# Cthulhu_Shield_Rev2f.net
KiCad netlist of a schematic drawn in EAGLE
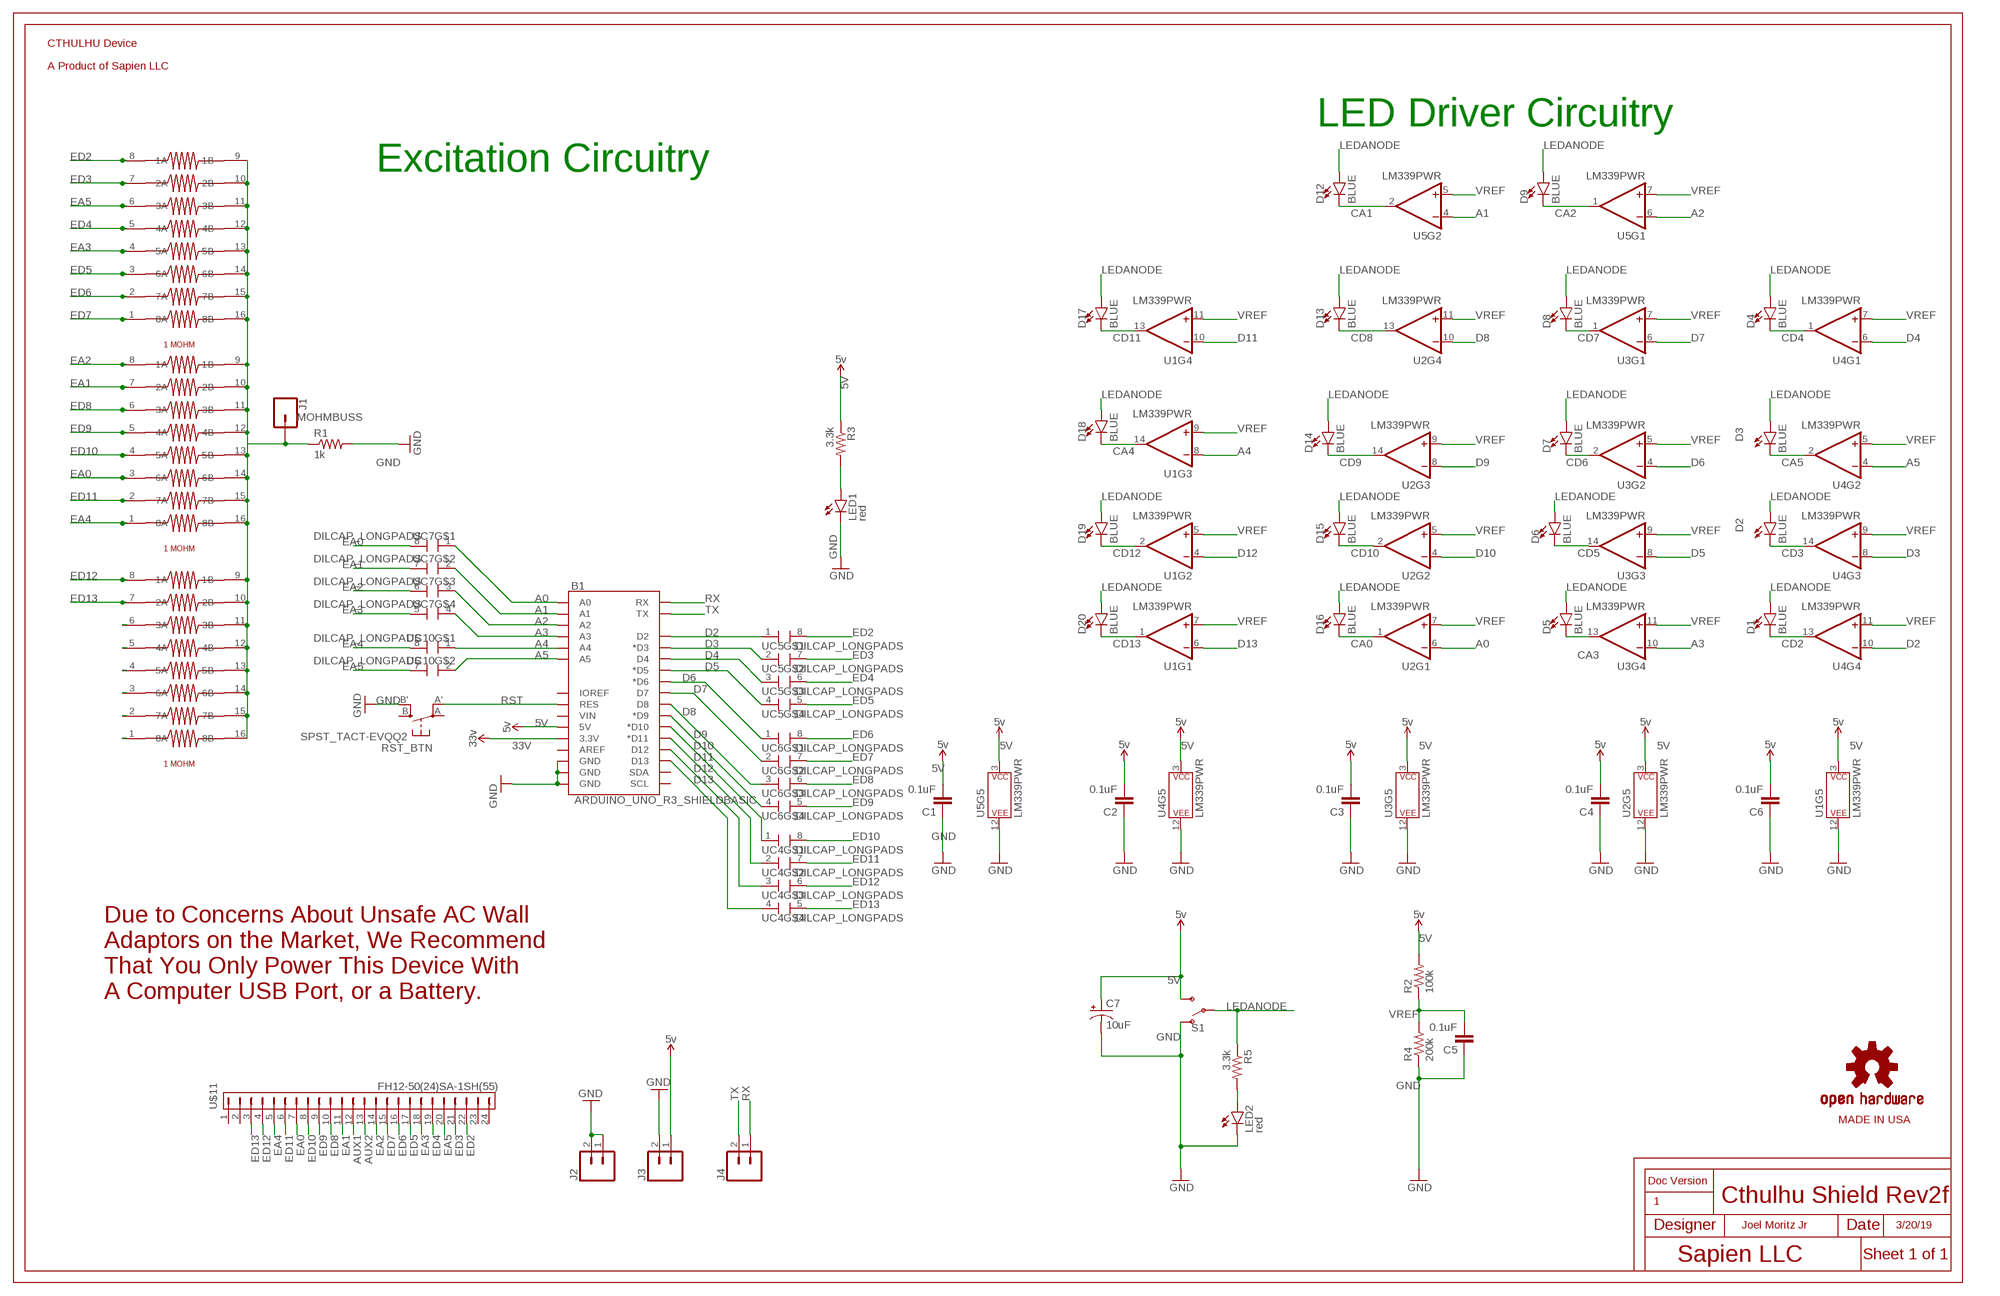
[diagram p0: schematic, sheet 1]

(export (version "E")
  (design (tool "Eeschema 10.0.6"))
  (components
    (comp (ref "B1")
      (value "ARDUINO_UNO_R3_SHIELDBASIC")
      (footprint "eagle-import:UNO_R3_SHIELD")
      (libsource (lib "eagle-import") (part "ARDUINO_UNO_R3_SHIELDBASIC"))
    )
    (comp (ref "C1")
      (value "0.1uF")
      (footprint "eagle-import:0603")
      (libsource (lib "eagle-import") (part "0.1UF-0603-25V-(+80/-20%)"))
    )
    (comp (ref "C2")
      (value "0.1uF")
      (footprint "eagle-import:0603")
      (libsource (lib "eagle-import") (part "0.1UF-0603-25V-(+80/-20%)"))
    )
    (comp (ref "C3")
      (value "0.1uF")
      (footprint "eagle-import:0603")
      (libsource (lib "eagle-import") (part "0.1UF-0603-25V-(+80/-20%)"))
    )
    (comp (ref "C4")
      (value "0.1uF")
      (footprint "eagle-import:0603")
      (libsource (lib "eagle-import") (part "0.1UF-0603-25V-(+80/-20%)"))
    )
    (comp (ref "C5")
      (value "0.1uF")
      (footprint "eagle-import:0603")
      (libsource (lib "eagle-import") (part "0.1UF-0603-25V-(+80/-20%)"))
    )
    (comp (ref "C6")
      (value "0.1uF")
      (footprint "eagle-import:0603")
      (libsource (lib "eagle-import") (part "0.1UF-0603-25V-(+80/-20%)"))
    )
    (comp (ref "C7")
      (value "10uF")
      (footprint "eagle-import:EIA3528")
      (libsource (lib "eagle-import") (part "10UF-POLAR-EIA3528-20V-10%(TANT)"))
    )
    (comp (ref "D1")
      (value "BLUE")
      (footprint "eagle-import:LED-0603")
      (libsource (lib "eagle-import") (part "LED-BLUE0603"))
    )
    (comp (ref "D2")
      (value "BLUE")
      (footprint "eagle-import:LED-0603")
      (libsource (lib "eagle-import") (part "LED-BLUE0603"))
    )
    (comp (ref "D3")
      (value "BLUE")
      (footprint "eagle-import:LED-0603")
      (libsource (lib "eagle-import") (part "LED-BLUE0603"))
    )
    (comp (ref "D4")
      (value "BLUE")
      (footprint "eagle-import:LED-0603")
      (libsource (lib "eagle-import") (part "LED-BLUE0603"))
    )
    (comp (ref "D5")
      (value "BLUE")
      (footprint "eagle-import:LED-0603")
      (libsource (lib "eagle-import") (part "LED-BLUE0603"))
    )
    (comp (ref "D6")
      (value "BLUE")
      (footprint "eagle-import:LED-0603")
      (libsource (lib "eagle-import") (part "LED-BLUE0603"))
    )
    (comp (ref "D7")
      (value "BLUE")
      (footprint "eagle-import:LED-0603")
      (libsource (lib "eagle-import") (part "LED-BLUE0603"))
    )
    (comp (ref "D8")
      (value "BLUE")
      (footprint "eagle-import:LED-0603")
      (libsource (lib "eagle-import") (part "LED-BLUE0603"))
    )
    (comp (ref "D9")
      (value "BLUE")
      (footprint "eagle-import:LED-0603")
      (libsource (lib "eagle-import") (part "LED-BLUE0603"))
    )
    (comp (ref "D12")
      (value "BLUE")
      (footprint "eagle-import:LED-0603")
      (libsource (lib "eagle-import") (part "LED-BLUE0603"))
    )
    (comp (ref "D13")
      (value "BLUE")
      (footprint "eagle-import:LED-0603")
      (libsource (lib "eagle-import") (part "LED-BLUE0603"))
    )
    (comp (ref "D14")
      (value "BLUE")
      (footprint "eagle-import:LED-0603")
      (libsource (lib "eagle-import") (part "LED-BLUE0603"))
    )
    (comp (ref "D15")
      (value "BLUE")
      (footprint "eagle-import:LED-0603")
      (libsource (lib "eagle-import") (part "LED-BLUE0603"))
    )
    (comp (ref "D16")
      (value "BLUE")
      (footprint "eagle-import:LED-0603")
      (libsource (lib "eagle-import") (part "LED-BLUE0603"))
    )
    (comp (ref "D17")
      (value "BLUE")
      (footprint "eagle-import:LED-0603")
      (libsource (lib "eagle-import") (part "LED-BLUE0603"))
    )
    (comp (ref "D18")
      (value "BLUE")
      (footprint "eagle-import:LED-0603")
      (libsource (lib "eagle-import") (part "LED-BLUE0603"))
    )
    (comp (ref "D19")
      (value "BLUE")
      (footprint "eagle-import:LED-0603")
      (libsource (lib "eagle-import") (part "LED-BLUE0603"))
    )
    (comp (ref "D20")
      (value "BLUE")
      (footprint "eagle-import:LED-0603")
      (libsource (lib "eagle-import") (part "LED-BLUE0603"))
    )
    (comp (ref "J1")
      (value "CONN_01")
      (footprint "eagle-import:1X01")
      (libsource (lib "eagle-import") (part "CONN_01"))
    )
    (comp (ref "J2")
      (value "CONN_02")
      (footprint "eagle-import:1X02")
      (libsource (lib "eagle-import") (part "CONN_02"))
    )
    (comp (ref "J3")
      (value "CONN_02")
      (footprint "eagle-import:1X02")
      (libsource (lib "eagle-import") (part "CONN_02"))
    )
    (comp (ref "J4")
      (value "CONN_02")
      (footprint "eagle-import:1X02")
      (libsource (lib "eagle-import") (part "CONN_02"))
    )
    (comp (ref "LED1")
      (value "red")
      (footprint "eagle-import:LED-1206")
      (libsource (lib "eagle-import") (part "LED1206"))
    )
    (comp (ref "LED2")
      (value "red")
      (footprint "eagle-import:LED-1206")
      (libsource (lib "eagle-import") (part "LED1206"))
    )
    (comp (ref "LOGO1")
      (value "OSHW-LOGOL")
      (footprint "eagle-import:OSHW-LOGO-L")
      (libsource (lib "eagle-import") (part "OSHW-LOGOL"))
    )
    (comp (ref "R1")
      (value "1k")
      (footprint "eagle-import:0402")
      (libsource (lib "eagle-import") (part "RESISTOR0402"))
    )
    (comp (ref "R2")
      (value "100k")
      (footprint "eagle-import:0402")
      (libsource (lib "eagle-import") (part "RESISTOR0402"))
    )
    (comp (ref "R3")
      (value "3.3k")
      (footprint "eagle-import:0402")
      (libsource (lib "eagle-import") (part "RESISTOR0402"))
    )
    (comp (ref "R4")
      (value "200k")
      (footprint "eagle-import:0402")
      (libsource (lib "eagle-import") (part "RESISTOR0402"))
    )
    (comp (ref "R5")
      (value "3.3k")
      (footprint "eagle-import:0402")
      (libsource (lib "eagle-import") (part "RESISTOR0402"))
    )
    (comp (ref "RST_BTN")
      (value "SPST_TACT-EVQQ2")
      (footprint "eagle-import:EVQ-Q2")
      (libsource (lib "eagle-import") (part "SPST_TACT-EVQQ2"))
    )
    (comp (ref "S1")
      (value "SWITCH-SPDT-SMD-AYZ0202")
      (footprint "eagle-import:SWITCH_DPDT_SMD_AYZ0202")
      (libsource (lib "eagle-import") (part "SWITCH-SPDT-SMD-AYZ0202"))
    )
    (comp (ref "U$1")
      (value "1MOHM8")
      (footprint "eagle-import:JJ_CUSTOM_PARTS_1MOHMARRAY")
      (libsource (lib "eagle-import") (part "1MOHM8"))
    )
    (comp (ref "U$2")
      (value "1MOHM8")
      (footprint "eagle-import:JJ_CUSTOM_PARTS_1MOHMARRAY")
      (libsource (lib "eagle-import") (part "1MOHM8"))
    )
    (comp (ref "U$3")
      (value "1MOHM8")
      (footprint "eagle-import:JJ_CUSTOM_PARTS_1MOHMARRAY")
      (libsource (lib "eagle-import") (part "1MOHM8"))
    )
    (comp (ref "U$4")
      (value "NO_WALL_ADAPTOR")
      (footprint "eagle-import:NO_WALL_ADAPTOR")
      (libsource (lib "eagle-import") (part "NO_WALL_ADAPTOR"))
    )
    (comp (ref "U$5")
      (value "MADEINUSA")
      (footprint "eagle-import:MADEINUSA")
      (libsource (lib "eagle-import") (part "MADEINUSA"))
    )
    (comp (ref "U$8")
      (value "SAPEIN_LOGO_BOTTOM")
      (footprint "eagle-import:SAPIEN_LOGO_BOTTOM")
      (libsource (lib "eagle-import") (part "SAPEIN_LOGO_BOTTOM"))
    )
    (comp (ref "U$9")
      (value "CTHULHU_LOGO")
      (footprint "eagle-import:CTHULHU")
      (libsource (lib "eagle-import") (part "CTHULHU_LOGO"))
    )
    (comp (ref "U$11")
      (value "FH12-50(24)SA-1SH(55)")
      (footprint "eagle-import:FH12-16S-1SH")
      (libsource (lib "eagle-import") (part "FH12-50(24)SA-1SH(55)"))
    )
    (comp (ref "U1")
      (value "LM339PWR")
      (footprint "eagle-import:TSSOP-14")
      (libsource (lib "eagle-import") (part "LM339"))
    )
    (comp (ref "U2")
      (value "LM339PWR")
      (footprint "eagle-import:TSSOP-14")
      (libsource (lib "eagle-import") (part "LM339"))
    )
    (comp (ref "U3")
      (value "LM339PWR")
      (footprint "eagle-import:TSSOP-14")
      (libsource (lib "eagle-import") (part "LM339"))
    )
    (comp (ref "U4")
      (value "LM339PWR")
      (footprint "eagle-import:TSSOP-14")
      (libsource (lib "eagle-import") (part "LM339"))
    )
    (comp (ref "U5")
      (value "LM339PWR")
      (footprint "eagle-import:TSSOP-14")
      (libsource (lib "eagle-import") (part "LM339"))
    )
    (comp (ref "UC4")
      (value "DILCAP_LONGPADS")
      (footprint "eagle-import:RESISTOR-DIL_4X0402ARV341_LONGPADS")
      (libsource (lib "eagle-import") (part "DILCAP_LONGPADS"))
    )
    (comp (ref "UC5")
      (value "DILCAP_LONGPADS")
      (footprint "eagle-import:RESISTOR-DIL_4X0402ARV341_LONGPADS")
      (libsource (lib "eagle-import") (part "DILCAP_LONGPADS"))
    )
    (comp (ref "UC6")
      (value "DILCAP_LONGPADS")
      (footprint "eagle-import:RESISTOR-DIL_4X0402ARV341_LONGPADS")
      (libsource (lib "eagle-import") (part "DILCAP_LONGPADS"))
    )
    (comp (ref "UC7")
      (value "DILCAP_LONGPADS")
      (footprint "eagle-import:RESISTOR-DIL_4X0402ARV341_LONGPADS")
      (libsource (lib "eagle-import") (part "DILCAP_LONGPADS"))
    )
    (comp (ref "UC10")
      (value "DILCAP_LONGPADS")
      (footprint "eagle-import:RESISTOR-DIL_4X0402ARV341_LONGPADS")
      (libsource (lib "eagle-import") (part "DILCAP_LONGPADS"))
    )
  )
  (nets
    (net (code "1") (name "/A0") (class "Default")
      (node (ref "B1") (pin "A0") (pinfunction "A0_A0") (pintype "bidirectional"))
      (node (ref "U2") (pin "6") (pinfunction "-IN_6") (pintype "input"))
      (node (ref "UC7") (pin "1") (pinfunction "1_1") (pintype "passive"))
    )
    (net (code "2") (name "/A1") (class "Default")
      (node (ref "B1") (pin "A1") (pinfunction "A1_A1") (pintype "bidirectional"))
      (node (ref "U5") (pin "4") (pinfunction "-IN_4") (pintype "input"))
      (node (ref "UC7") (pin "2") (pinfunction "1_2") (pintype "passive"))
    )
    (net (code "3") (name "/A2") (class "Default")
      (node (ref "B1") (pin "A2") (pinfunction "A2_A2") (pintype "bidirectional"))
      (node (ref "U5") (pin "6") (pinfunction "-IN_6") (pintype "input"))
      (node (ref "UC7") (pin "3") (pinfunction "1_3") (pintype "passive"))
    )
    (net (code "4") (name "/A3") (class "Default")
      (node (ref "B1") (pin "A3") (pinfunction "A3_A3") (pintype "bidirectional"))
      (node (ref "U3") (pin "10") (pinfunction "-IN_10") (pintype "input"))
      (node (ref "UC7") (pin "4") (pinfunction "1_4") (pintype "passive"))
    )
    (net (code "5") (name "/A4") (class "Default")
      (node (ref "B1") (pin "A4") (pinfunction "A4_A4") (pintype "bidirectional"))
      (node (ref "U1") (pin "8") (pinfunction "-IN_8") (pintype "input"))
      (node (ref "UC10") (pin "1") (pinfunction "1_1") (pintype "passive"))
    )
    (net (code "6") (name "/A5") (class "Default")
      (node (ref "B1") (pin "A5") (pinfunction "A5_A5") (pintype "bidirectional"))
      (node (ref "U4") (pin "4") (pinfunction "-IN_4") (pintype "input"))
      (node (ref "UC10") (pin "2") (pinfunction "1_2") (pintype "passive"))
    )
    (net (code "7") (name "/AUX1") (class "Default")
      (node (ref "U$11") (pin "12") (pinfunction "12_12") (pintype "passive"))
    )
    (net (code "8") (name "/AUX2") (class "Default")
      (node (ref "U$11") (pin "13") (pinfunction "13_13") (pintype "passive"))
    )
    (net (code "9") (name "/CA0") (class "Default")
      (node (ref "D16") (pin "C") (pinfunction "C_C") (pintype "passive"))
      (node (ref "U2") (pin "1") (pinfunction "OUT_1") (pintype "output"))
    )
    (net (code "10") (name "/CA1") (class "Default")
      (node (ref "D12") (pin "C") (pinfunction "C_C") (pintype "passive"))
      (node (ref "U5") (pin "2") (pinfunction "OUT_2") (pintype "output"))
    )
    (net (code "11") (name "/CA2") (class "Default")
      (node (ref "D9") (pin "C") (pinfunction "C_C") (pintype "passive"))
      (node (ref "U5") (pin "1") (pinfunction "OUT_1") (pintype "output"))
    )
    (net (code "12") (name "/CA3") (class "Default")
      (node (ref "D5") (pin "C") (pinfunction "C_C") (pintype "passive"))
      (node (ref "U3") (pin "13") (pinfunction "OUT_13") (pintype "output"))
    )
    (net (code "13") (name "/CA4") (class "Default")
      (node (ref "D18") (pin "C") (pinfunction "C_C") (pintype "passive"))
      (node (ref "U1") (pin "14") (pinfunction "OUT_14") (pintype "output"))
    )
    (net (code "14") (name "/CA5") (class "Default")
      (node (ref "D3") (pin "C") (pinfunction "C_C") (pintype "passive"))
      (node (ref "U4") (pin "2") (pinfunction "OUT_2") (pintype "output"))
    )
    (net (code "15") (name "/CD2") (class "Default")
      (node (ref "D1") (pin "C") (pinfunction "C_C") (pintype "passive"))
      (node (ref "U4") (pin "13") (pinfunction "OUT_13") (pintype "output"))
    )
    (net (code "16") (name "/CD3") (class "Default")
      (node (ref "D2") (pin "C") (pinfunction "C_C") (pintype "passive"))
      (node (ref "U4") (pin "14") (pinfunction "OUT_14") (pintype "output"))
    )
    (net (code "17") (name "/CD4") (class "Default")
      (node (ref "D4") (pin "C") (pinfunction "C_C") (pintype "passive"))
      (node (ref "U4") (pin "1") (pinfunction "OUT_1") (pintype "output"))
    )
    (net (code "18") (name "/CD5") (class "Default")
      (node (ref "D6") (pin "C") (pinfunction "C_C") (pintype "passive"))
      (node (ref "U3") (pin "14") (pinfunction "OUT_14") (pintype "output"))
    )
    (net (code "19") (name "/CD6") (class "Default")
      (node (ref "D7") (pin "C") (pinfunction "C_C") (pintype "passive"))
      (node (ref "U3") (pin "2") (pinfunction "OUT_2") (pintype "output"))
    )
    (net (code "20") (name "/CD7") (class "Default")
      (node (ref "D8") (pin "C") (pinfunction "C_C") (pintype "passive"))
      (node (ref "U3") (pin "1") (pinfunction "OUT_1") (pintype "output"))
    )
    (net (code "21") (name "/CD8") (class "Default")
      (node (ref "D13") (pin "C") (pinfunction "C_C") (pintype "passive"))
      (node (ref "U2") (pin "13") (pinfunction "OUT_13") (pintype "output"))
    )
    (net (code "22") (name "/CD9") (class "Default")
      (node (ref "D14") (pin "C") (pinfunction "C_C") (pintype "passive"))
      (node (ref "U2") (pin "14") (pinfunction "OUT_14") (pintype "output"))
    )
    (net (code "23") (name "/CD10") (class "Default")
      (node (ref "D15") (pin "C") (pinfunction "C_C") (pintype "passive"))
      (node (ref "U2") (pin "2") (pinfunction "OUT_2") (pintype "output"))
    )
    (net (code "24") (name "/CD11") (class "Default")
      (node (ref "D17") (pin "C") (pinfunction "C_C") (pintype "passive"))
      (node (ref "U1") (pin "13") (pinfunction "OUT_13") (pintype "output"))
    )
    (net (code "25") (name "/CD12") (class "Default")
      (node (ref "D19") (pin "C") (pinfunction "C_C") (pintype "passive"))
      (node (ref "U1") (pin "2") (pinfunction "OUT_2") (pintype "output"))
    )
    (net (code "26") (name "/CD13") (class "Default")
      (node (ref "D20") (pin "C") (pinfunction "C_C") (pintype "passive"))
      (node (ref "U1") (pin "1") (pinfunction "OUT_1") (pintype "output"))
    )
    (net (code "27") (name "/D2") (class "Default")
      (node (ref "B1") (pin "D2") (pinfunction "D2_D2") (pintype "bidirectional"))
      (node (ref "U4") (pin "10") (pinfunction "-IN_10") (pintype "input"))
      (node (ref "UC5") (pin "1") (pinfunction "1_1") (pintype "passive"))
    )
    (net (code "28") (name "/D3") (class "Default")
      (node (ref "B1") (pin "D3") (pinfunction "*D3_D3") (pintype "bidirectional"))
      (node (ref "U4") (pin "8") (pinfunction "-IN_8") (pintype "input"))
      (node (ref "UC5") (pin "2") (pinfunction "1_2") (pintype "passive"))
    )
    (net (code "29") (name "/D4") (class "Default")
      (node (ref "B1") (pin "D4") (pinfunction "D4_D4") (pintype "bidirectional"))
      (node (ref "U4") (pin "6") (pinfunction "-IN_6") (pintype "input"))
      (node (ref "UC5") (pin "3") (pinfunction "1_3") (pintype "passive"))
    )
    (net (code "30") (name "/D5") (class "Default")
      (node (ref "B1") (pin "D5") (pinfunction "*D5_D5") (pintype "bidirectional"))
      (node (ref "U3") (pin "8") (pinfunction "-IN_8") (pintype "input"))
      (node (ref "UC5") (pin "4") (pinfunction "1_4") (pintype "passive"))
    )
    (net (code "31") (name "/D6") (class "Default")
      (node (ref "B1") (pin "D6") (pinfunction "*D6_D6") (pintype "bidirectional"))
      (node (ref "U3") (pin "4") (pinfunction "-IN_4") (pintype "input"))
      (node (ref "UC6") (pin "1") (pinfunction "1_1") (pintype "passive"))
    )
    (net (code "32") (name "/D7") (class "Default")
      (node (ref "B1") (pin "D7") (pinfunction "D7_D7") (pintype "bidirectional"))
      (node (ref "U3") (pin "6") (pinfunction "-IN_6") (pintype "input"))
      (node (ref "UC6") (pin "2") (pinfunction "1_2") (pintype "passive"))
    )
    (net (code "33") (name "/D8") (class "Default")
      (node (ref "B1") (pin "D8") (pinfunction "D8_D8") (pintype "bidirectional"))
      (node (ref "U2") (pin "10") (pinfunction "-IN_10") (pintype "input"))
      (node (ref "UC6") (pin "3") (pinfunction "1_3") (pintype "passive"))
    )
    (net (code "34") (name "/D9") (class "Default")
      (node (ref "B1") (pin "D9") (pinfunction "*D9_D9") (pintype "bidirectional"))
      (node (ref "U2") (pin "8") (pinfunction "-IN_8") (pintype "input"))
      (node (ref "UC6") (pin "4") (pinfunction "1_4") (pintype "passive"))
    )
    (net (code "35") (name "/D10") (class "Default")
      (node (ref "B1") (pin "D10") (pinfunction "*D10_D10") (pintype "bidirectional"))
      (node (ref "U2") (pin "4") (pinfunction "-IN_4") (pintype "input"))
      (node (ref "UC4") (pin "1") (pinfunction "1_1") (pintype "passive"))
    )
    (net (code "36") (name "/D11") (class "Default")
      (node (ref "B1") (pin "D11") (pinfunction "*D11_D11") (pintype "bidirectional"))
      (node (ref "U1") (pin "10") (pinfunction "-IN_10") (pintype "input"))
      (node (ref "UC4") (pin "2") (pinfunction "1_2") (pintype "passive"))
    )
    (net (code "37") (name "/D12") (class "Default")
      (node (ref "B1") (pin "D12") (pinfunction "D12_D12") (pintype "bidirectional"))
      (node (ref "U1") (pin "4") (pinfunction "-IN_4") (pintype "input"))
      (node (ref "UC4") (pin "3") (pinfunction "1_3") (pintype "passive"))
    )
    (net (code "38") (name "/D13") (class "Default")
      (node (ref "B1") (pin "D13") (pinfunction "D13_D13") (pintype "bidirectional"))
      (node (ref "U1") (pin "6") (pinfunction "-IN_6") (pintype "input"))
      (node (ref "UC4") (pin "4") (pinfunction "1_4") (pintype "passive"))
    )
    (net (code "39") (name "/EA0") (class "Default")
      (node (ref "U$11") (pin "7") (pinfunction "7_7") (pintype "passive"))
      (node (ref "U$2") (pin "3") (pinfunction "6A_3") (pintype "bidirectional"))
      (node (ref "UC7") (pin "8") (pinfunction "2_8") (pintype "passive"))
    )
    (net (code "40") (name "/EA1") (class "Default")
      (node (ref "U$11") (pin "11") (pinfunction "11_11") (pintype "passive"))
      (node (ref "U$2") (pin "7") (pinfunction "2A_7") (pintype "bidirectional"))
      (node (ref "UC7") (pin "7") (pinfunction "2_7") (pintype "passive"))
    )
    (net (code "41") (name "/EA2") (class "Default")
      (node (ref "U$11") (pin "14") (pinfunction "14_14") (pintype "passive"))
      (node (ref "U$2") (pin "8") (pinfunction "1A_8") (pintype "bidirectional"))
      (node (ref "UC7") (pin "6") (pinfunction "2_6") (pintype "passive"))
    )
    (net (code "42") (name "/EA3") (class "Default")
      (node (ref "U$1") (pin "4") (pinfunction "5A_4") (pintype "bidirectional"))
      (node (ref "U$11") (pin "18") (pinfunction "18_18") (pintype "passive"))
      (node (ref "UC7") (pin "5") (pinfunction "2_5") (pintype "passive"))
    )
    (net (code "43") (name "/EA4") (class "Default")
      (node (ref "U$11") (pin "5") (pinfunction "5_5") (pintype "passive"))
      (node (ref "U$2") (pin "1") (pinfunction "8A_1") (pintype "bidirectional"))
      (node (ref "UC10") (pin "8") (pinfunction "2_8") (pintype "passive"))
    )
    (net (code "44") (name "/EA5") (class "Default")
      (node (ref "U$1") (pin "6") (pinfunction "3A_6") (pintype "bidirectional"))
      (node (ref "U$11") (pin "20") (pinfunction "20_20") (pintype "passive"))
      (node (ref "UC10") (pin "7") (pinfunction "2_7") (pintype "passive"))
    )
    (net (code "45") (name "/ED2") (class "Default")
      (node (ref "U$1") (pin "8") (pinfunction "1A_8") (pintype "bidirectional"))
      (node (ref "U$11") (pin "22") (pinfunction "22_22") (pintype "passive"))
      (node (ref "UC5") (pin "8") (pinfunction "2_8") (pintype "passive"))
    )
    (net (code "46") (name "/ED3") (class "Default")
      (node (ref "U$1") (pin "7") (pinfunction "2A_7") (pintype "bidirectional"))
      (node (ref "U$11") (pin "21") (pinfunction "21_21") (pintype "passive"))
      (node (ref "UC5") (pin "7") (pinfunction "2_7") (pintype "passive"))
    )
    (net (code "47") (name "/ED4") (class "Default")
      (node (ref "U$1") (pin "5") (pinfunction "4A_5") (pintype "bidirectional"))
      (node (ref "U$11") (pin "19") (pinfunction "19_19") (pintype "passive"))
      (node (ref "UC5") (pin "6") (pinfunction "2_6") (pintype "passive"))
    )
    (net (code "48") (name "/ED5") (class "Default")
      (node (ref "U$1") (pin "3") (pinfunction "6A_3") (pintype "bidirectional"))
      (node (ref "U$11") (pin "17") (pinfunction "17_17") (pintype "passive"))
      (node (ref "UC5") (pin "5") (pinfunction "2_5") (pintype "passive"))
    )
    (net (code "49") (name "/ED6") (class "Default")
      (node (ref "U$1") (pin "2") (pinfunction "7A_2") (pintype "bidirectional"))
      (node (ref "U$11") (pin "16") (pinfunction "16_16") (pintype "passive"))
      (node (ref "UC6") (pin "8") (pinfunction "2_8") (pintype "passive"))
    )
    (net (code "50") (name "/ED7") (class "Default")
      (node (ref "U$1") (pin "1") (pinfunction "8A_1") (pintype "bidirectional"))
      (node (ref "U$11") (pin "15") (pinfunction "15_15") (pintype "passive"))
      (node (ref "UC6") (pin "7") (pinfunction "2_7") (pintype "passive"))
    )
    (net (code "51") (name "/ED8") (class "Default")
      (node (ref "U$11") (pin "10") (pinfunction "10_10") (pintype "passive"))
      (node (ref "U$2") (pin "6") (pinfunction "3A_6") (pintype "bidirectional"))
      (node (ref "UC6") (pin "6") (pinfunction "2_6") (pintype "passive"))
    )
    (net (code "52") (name "/ED9") (class "Default")
      (node (ref "U$11") (pin "9") (pinfunction "9_9") (pintype "passive"))
      (node (ref "U$2") (pin "5") (pinfunction "4A_5") (pintype "bidirectional"))
      (node (ref "UC6") (pin "5") (pinfunction "2_5") (pintype "passive"))
    )
    (net (code "53") (name "/ED10") (class "Default")
      (node (ref "U$11") (pin "8") (pinfunction "8_8") (pintype "passive"))
      (node (ref "U$2") (pin "4") (pinfunction "5A_4") (pintype "bidirectional"))
      (node (ref "UC4") (pin "8") (pinfunction "2_8") (pintype "passive"))
    )
    (net (code "54") (name "/ED11") (class "Default")
      (node (ref "U$11") (pin "6") (pinfunction "6_6") (pintype "passive"))
      (node (ref "U$2") (pin "2") (pinfunction "7A_2") (pintype "bidirectional"))
      (node (ref "UC4") (pin "7") (pinfunction "2_7") (pintype "passive"))
    )
    (net (code "55") (name "/ED12") (class "Default")
      (node (ref "U$11") (pin "4") (pinfunction "4_4") (pintype "passive"))
      (node (ref "U$3") (pin "8") (pinfunction "1A_8") (pintype "bidirectional"))
      (node (ref "UC4") (pin "6") (pinfunction "2_6") (pintype "passive"))
    )
    (net (code "56") (name "/ED13") (class "Default")
      (node (ref "U$11") (pin "3") (pinfunction "3_3") (pintype "passive"))
      (node (ref "U$3") (pin "7") (pinfunction "2A_7") (pintype "bidirectional"))
      (node (ref "UC4") (pin "5") (pinfunction "2_5") (pintype "passive"))
    )
    (net (code "57") (name "/LEDANODE") (class "Default")
      (node (ref "D1") (pin "A") (pinfunction "A_A") (pintype "passive"))
      (node (ref "D12") (pin "A") (pinfunction "A_A") (pintype "passive"))
      (node (ref "D13") (pin "A") (pinfunction "A_A") (pintype "passive"))
      (node (ref "D14") (pin "A") (pinfunction "A_A") (pintype "passive"))
      (node (ref "D15") (pin "A") (pinfunction "A_A") (pintype "passive"))
      (node (ref "D16") (pin "A") (pinfunction "A_A") (pintype "passive"))
      (node (ref "D17") (pin "A") (pinfunction "A_A") (pintype "passive"))
      (node (ref "D18") (pin "A") (pinfunction "A_A") (pintype "passive"))
      (node (ref "D19") (pin "A") (pinfunction "A_A") (pintype "passive"))
      (node (ref "D2") (pin "A") (pinfunction "A_A") (pintype "passive"))
      (node (ref "D20") (pin "A") (pinfunction "A_A") (pintype "passive"))
      (node (ref "D3") (pin "A") (pinfunction "A_A") (pintype "passive"))
      (node (ref "D4") (pin "A") (pinfunction "A_A") (pintype "passive"))
      (node (ref "D5") (pin "A") (pinfunction "A_A") (pintype "passive"))
      (node (ref "D6") (pin "A") (pinfunction "A_A") (pintype "passive"))
      (node (ref "D7") (pin "A") (pinfunction "A_A") (pintype "passive"))
      (node (ref "D8") (pin "A") (pinfunction "A_A") (pintype "passive"))
      (node (ref "D9") (pin "A") (pinfunction "A_A") (pintype "passive"))
      (node (ref "R5") (pin "1") (pinfunction "1_1") (pintype "passive"))
      (node (ref "S1") (pin "2") (pinfunction "P_2") (pintype "passive"))
    )
    (net (code "58") (name "/MOHMBUSS") (class "Default")
      (node (ref "J1") (pin "1") (pinfunction "1_1") (pintype "passive"))
      (node (ref "R1") (pin "1") (pinfunction "1_1") (pintype "passive"))
      (node (ref "U$1") (pin "10") (pinfunction "2B_10") (pintype "bidirectional"))
      (node (ref "U$1") (pin "11") (pinfunction "3B_11") (pintype "bidirectional"))
      (node (ref "U$1") (pin "12") (pinfunction "4B_12") (pintype "bidirectional"))
      (node (ref "U$1") (pin "13") (pinfunction "5B_13") (pintype "bidirectional"))
      (node (ref "U$1") (pin "14") (pinfunction "6B_14") (pintype "bidirectional"))
      (node (ref "U$1") (pin "15") (pinfunction "7B_15") (pintype "bidirectional"))
      (node (ref "U$1") (pin "16") (pinfunction "8B_16") (pintype "bidirectional"))
      (node (ref "U$1") (pin "9") (pinfunction "1B_9") (pintype "bidirectional"))
      (node (ref "U$2") (pin "10") (pinfunction "2B_10") (pintype "bidirectional"))
      (node (ref "U$2") (pin "11") (pinfunction "3B_11") (pintype "bidirectional"))
      (node (ref "U$2") (pin "12") (pinfunction "4B_12") (pintype "bidirectional"))
      (node (ref "U$2") (pin "13") (pinfunction "5B_13") (pintype "bidirectional"))
      (node (ref "U$2") (pin "14") (pinfunction "6B_14") (pintype "bidirectional"))
      (node (ref "U$2") (pin "15") (pinfunction "7B_15") (pintype "bidirectional"))
      (node (ref "U$2") (pin "16") (pinfunction "8B_16") (pintype "bidirectional"))
      (node (ref "U$2") (pin "9") (pinfunction "1B_9") (pintype "bidirectional"))
      (node (ref "U$3") (pin "10") (pinfunction "2B_10") (pintype "bidirectional"))
      (node (ref "U$3") (pin "11") (pinfunction "3B_11") (pintype "bidirectional"))
      (node (ref "U$3") (pin "12") (pinfunction "4B_12") (pintype "bidirectional"))
      (node (ref "U$3") (pin "13") (pinfunction "5B_13") (pintype "bidirectional"))
      (node (ref "U$3") (pin "14") (pinfunction "6B_14") (pintype "bidirectional"))
      (node (ref "U$3") (pin "15") (pinfunction "7B_15") (pintype "bidirectional"))
      (node (ref "U$3") (pin "16") (pinfunction "8B_16") (pintype "bidirectional"))
      (node (ref "U$3") (pin "9") (pinfunction "1B_9") (pintype "bidirectional"))
    )
    (net (code "59") (name "/RST") (class "Default")
      (node (ref "B1") (pin "RES") (pinfunction "RES_RES") (pintype "bidirectional"))
      (node (ref "RST_BTN") (pin "A'") (pinfunction "P1_A'") (pintype "passive"))
    )
    (net (code "60") (name "/RX") (class "Default")
      (node (ref "B1") (pin "RX") (pinfunction "RX_RX") (pintype "bidirectional"))
      (node (ref "J4") (pin "1") (pinfunction "1_1") (pintype "passive"))
    )
    (net (code "61") (name "/TX") (class "Default")
      (node (ref "B1") (pin "TX") (pinfunction "TX_TX") (pintype "bidirectional"))
      (node (ref "J4") (pin "2") (pinfunction "2_2") (pintype "passive"))
    )
    (net (code "62") (name "/VREF") (class "Default")
      (node (ref "C5") (pin "2") (pinfunction "2_2") (pintype "passive"))
      (node (ref "R2") (pin "1") (pinfunction "1_1") (pintype "passive"))
      (node (ref "R4") (pin "2") (pinfunction "2_2") (pintype "passive"))
      (node (ref "U1") (pin "11") (pinfunction "+IN_11") (pintype "input"))
      (node (ref "U1") (pin "5") (pinfunction "+IN_5") (pintype "input"))
      (node (ref "U1") (pin "7") (pinfunction "+IN_7") (pintype "input"))
      (node (ref "U1") (pin "9") (pinfunction "+IN_9") (pintype "input"))
      (node (ref "U2") (pin "11") (pinfunction "+IN_11") (pintype "input"))
      (node (ref "U2") (pin "5") (pinfunction "+IN_5") (pintype "input"))
      (node (ref "U2") (pin "7") (pinfunction "+IN_7") (pintype "input"))
      (node (ref "U2") (pin "9") (pinfunction "+IN_9") (pintype "input"))
      (node (ref "U3") (pin "11") (pinfunction "+IN_11") (pintype "input"))
      (node (ref "U3") (pin "5") (pinfunction "+IN_5") (pintype "input"))
      (node (ref "U3") (pin "7") (pinfunction "+IN_7") (pintype "input"))
      (node (ref "U3") (pin "9") (pinfunction "+IN_9") (pintype "input"))
      (node (ref "U4") (pin "11") (pinfunction "+IN_11") (pintype "input"))
      (node (ref "U4") (pin "5") (pinfunction "+IN_5") (pintype "input"))
      (node (ref "U4") (pin "7") (pinfunction "+IN_7") (pintype "input"))
      (node (ref "U4") (pin "9") (pinfunction "+IN_9") (pintype "input"))
      (node (ref "U5") (pin "5") (pinfunction "+IN_5") (pintype "input"))
      (node (ref "U5") (pin "7") (pinfunction "+IN_7") (pintype "input"))
    )
    (net (code "63") (name "5v") (class "Default")
      (node (ref "B1") (pin "5V") (pinfunction "5V_5V") (pintype "bidirectional"))
      (node (ref "C1") (pin "2") (pinfunction "2_2") (pintype "passive"))
      (node (ref "C2") (pin "2") (pinfunction "2_2") (pintype "passive"))
      (node (ref "C3") (pin "2") (pinfunction "2_2") (pintype "passive"))
      (node (ref "C4") (pin "2") (pinfunction "2_2") (pintype "passive"))
      (node (ref "C6") (pin "2") (pinfunction "2_2") (pintype "passive"))
      (node (ref "C7") (pin "A") (pinfunction "+_A") (pintype "passive"))
      (node (ref "J3") (pin "1") (pinfunction "1_1") (pintype "passive"))
      (node (ref "R2") (pin "2") (pinfunction "2_2") (pintype "passive"))
      (node (ref "R3") (pin "1") (pinfunction "1_1") (pintype "passive"))
      (node (ref "S1") (pin "3") (pinfunction "S_3") (pintype "passive"))
      (node (ref "U1") (pin "3") (pinfunction "P$V+_3") (pintype "bidirectional"))
      (node (ref "U2") (pin "3") (pinfunction "P$V+_3") (pintype "bidirectional"))
      (node (ref "U3") (pin "3") (pinfunction "P$V+_3") (pintype "bidirectional"))
      (node (ref "U4") (pin "3") (pinfunction "P$V+_3") (pintype "bidirectional"))
      (node (ref "U5") (pin "3") (pinfunction "P$V+_3") (pintype "bidirectional"))
    )
    (net (code "64") (name "33v") (class "Default")
      (node (ref "B1") (pin "3.3V") (pinfunction "3.3V_3.3V") (pintype "bidirectional"))
    )
    (net (code "65") (name "GND") (class "Default")
      (node (ref "B1") (pin "GND@0") (pinfunction "GND_GND@0") (pintype "bidirectional"))
      (node (ref "B1") (pin "GND@1") (pinfunction "GND_GND@1") (pintype "bidirectional"))
      (node (ref "B1") (pin "GND@2") (pinfunction "GND_GND@2") (pintype "bidirectional"))
      (node (ref "C1") (pin "1") (pinfunction "1_1") (pintype "passive"))
      (node (ref "C2") (pin "1") (pinfunction "1_1") (pintype "passive"))
      (node (ref "C3") (pin "1") (pinfunction "1_1") (pintype "passive"))
      (node (ref "C4") (pin "1") (pinfunction "1_1") (pintype "passive"))
      (node (ref "C5") (pin "1") (pinfunction "1_1") (pintype "passive"))
      (node (ref "C6") (pin "1") (pinfunction "1_1") (pintype "passive"))
      (node (ref "C7") (pin "C") (pinfunction "-_C") (pintype "passive"))
      (node (ref "J2") (pin "1") (pinfunction "1_1") (pintype "passive"))
      (node (ref "J2") (pin "2") (pinfunction "2_2") (pintype "passive"))
      (node (ref "J3") (pin "2") (pinfunction "2_2") (pintype "passive"))
      (node (ref "LED1") (pin "C") (pinfunction "C_C") (pintype "passive"))
      (node (ref "LED2") (pin "C") (pinfunction "C_C") (pintype "passive"))
      (node (ref "R1") (pin "2") (pinfunction "2_2") (pintype "passive"))
      (node (ref "R4") (pin "1") (pinfunction "1_1") (pintype "passive"))
      (node (ref "RST_BTN") (pin "B'") (pinfunction "S1_B'") (pintype "passive"))
      (node (ref "S1") (pin "1") (pinfunction "O_1") (pintype "passive"))
      (node (ref "U1") (pin "12") (pinfunction "P$V-_12") (pintype "bidirectional"))
      (node (ref "U2") (pin "12") (pinfunction "P$V-_12") (pintype "bidirectional"))
      (node (ref "U3") (pin "12") (pinfunction "P$V-_12") (pintype "bidirectional"))
      (node (ref "U4") (pin "12") (pinfunction "P$V-_12") (pintype "bidirectional"))
      (node (ref "U5") (pin "12") (pinfunction "P$V-_12") (pintype "bidirectional"))
    )
    (net (code "66") (name "Net-(LED1-PadA)") (class "Default")
      (node (ref "LED1") (pin "A") (pinfunction "A_A") (pintype "passive"))
      (node (ref "R3") (pin "2") (pinfunction "2_2") (pintype "passive"))
    )
    (net (code "67") (name "Net-(LED2-PadA)") (class "Default")
      (node (ref "LED2") (pin "A") (pinfunction "A_A") (pintype "passive"))
      (node (ref "R5") (pin "2") (pinfunction "2_2") (pintype "passive"))
    )
    (net (code "68") (name "unconnected-(B1-PadAREF)") (class "Default")
      (node (ref "B1") (pin "AREF") (pinfunction "AREF_AREF") (pintype "bidirectional"))
    )
    (net (code "69") (name "unconnected-(B1-PadIOREF)") (class "Default")
      (node (ref "B1") (pin "IOREF") (pinfunction "IOREF_IOREF") (pintype "bidirectional"))
    )
    (net (code "70") (name "unconnected-(B1-PadSCL)") (class "Default")
      (node (ref "B1") (pin "SCL") (pinfunction "SCL_SCL") (pintype "bidirectional"))
    )
    (net (code "71") (name "unconnected-(B1-PadSDA)") (class "Default")
      (node (ref "B1") (pin "SDA") (pinfunction "SDA_SDA") (pintype "bidirectional"))
    )
    (net (code "72") (name "unconnected-(B1-PadVIN)") (class "Default")
      (node (ref "B1") (pin "VIN") (pinfunction "VIN_VIN") (pintype "bidirectional"))
    )
    (net (code "73") (name "unconnected-(RST_BTN-P-PadA)") (class "Default")
      (node (ref "RST_BTN") (pin "A") (pinfunction "P_A") (pintype "passive"))
    )
    (net (code "74") (name "unconnected-(RST_BTN-S-PadB)") (class "Default")
      (node (ref "RST_BTN") (pin "B") (pinfunction "S_B") (pintype "passive"))
    )
    (net (code "75") (name "unconnected-(U$3-3A-Pad6)") (class "Default")
      (node (ref "U$3") (pin "6") (pinfunction "3A_6") (pintype "bidirectional"))
    )
    (net (code "76") (name "unconnected-(U$3-4A-Pad5)") (class "Default")
      (node (ref "U$3") (pin "5") (pinfunction "4A_5") (pintype "bidirectional"))
    )
    (net (code "77") (name "unconnected-(U$3-5A-Pad4)") (class "Default")
      (node (ref "U$3") (pin "4") (pinfunction "5A_4") (pintype "bidirectional"))
    )
    (net (code "78") (name "unconnected-(U$3-6A-Pad3)") (class "Default")
      (node (ref "U$3") (pin "3") (pinfunction "6A_3") (pintype "bidirectional"))
    )
    (net (code "79") (name "unconnected-(U$3-7A-Pad2)") (class "Default")
      (node (ref "U$3") (pin "2") (pinfunction "7A_2") (pintype "bidirectional"))
    )
    (net (code "80") (name "unconnected-(U$3-8A-Pad1)") (class "Default")
      (node (ref "U$3") (pin "1") (pinfunction "8A_1") (pintype "bidirectional"))
    )
    (net (code "81") (name "unconnected-(U$11-Pad1)") (class "Default")
      (node (ref "U$11") (pin "1") (pinfunction "1_1") (pintype "passive"))
    )
    (net (code "82") (name "unconnected-(U$11-Pad2)") (class "Default")
      (node (ref "U$11") (pin "2") (pinfunction "2_2") (pintype "passive"))
    )
    (net (code "83") (name "unconnected-(U$11-Pad23)") (class "Default")
      (node (ref "U$11") (pin "23") (pinfunction "23_23") (pintype "passive"))
    )
    (net (code "84") (name "unconnected-(U$11-Pad24)") (class "Default")
      (node (ref "U$11") (pin "24") (pinfunction "24_24") (pintype "passive"))
    )
  )
)
